# MCU025B_F280049C_Device.net
KiCad netlist of a schematic drawn in Altium Designer
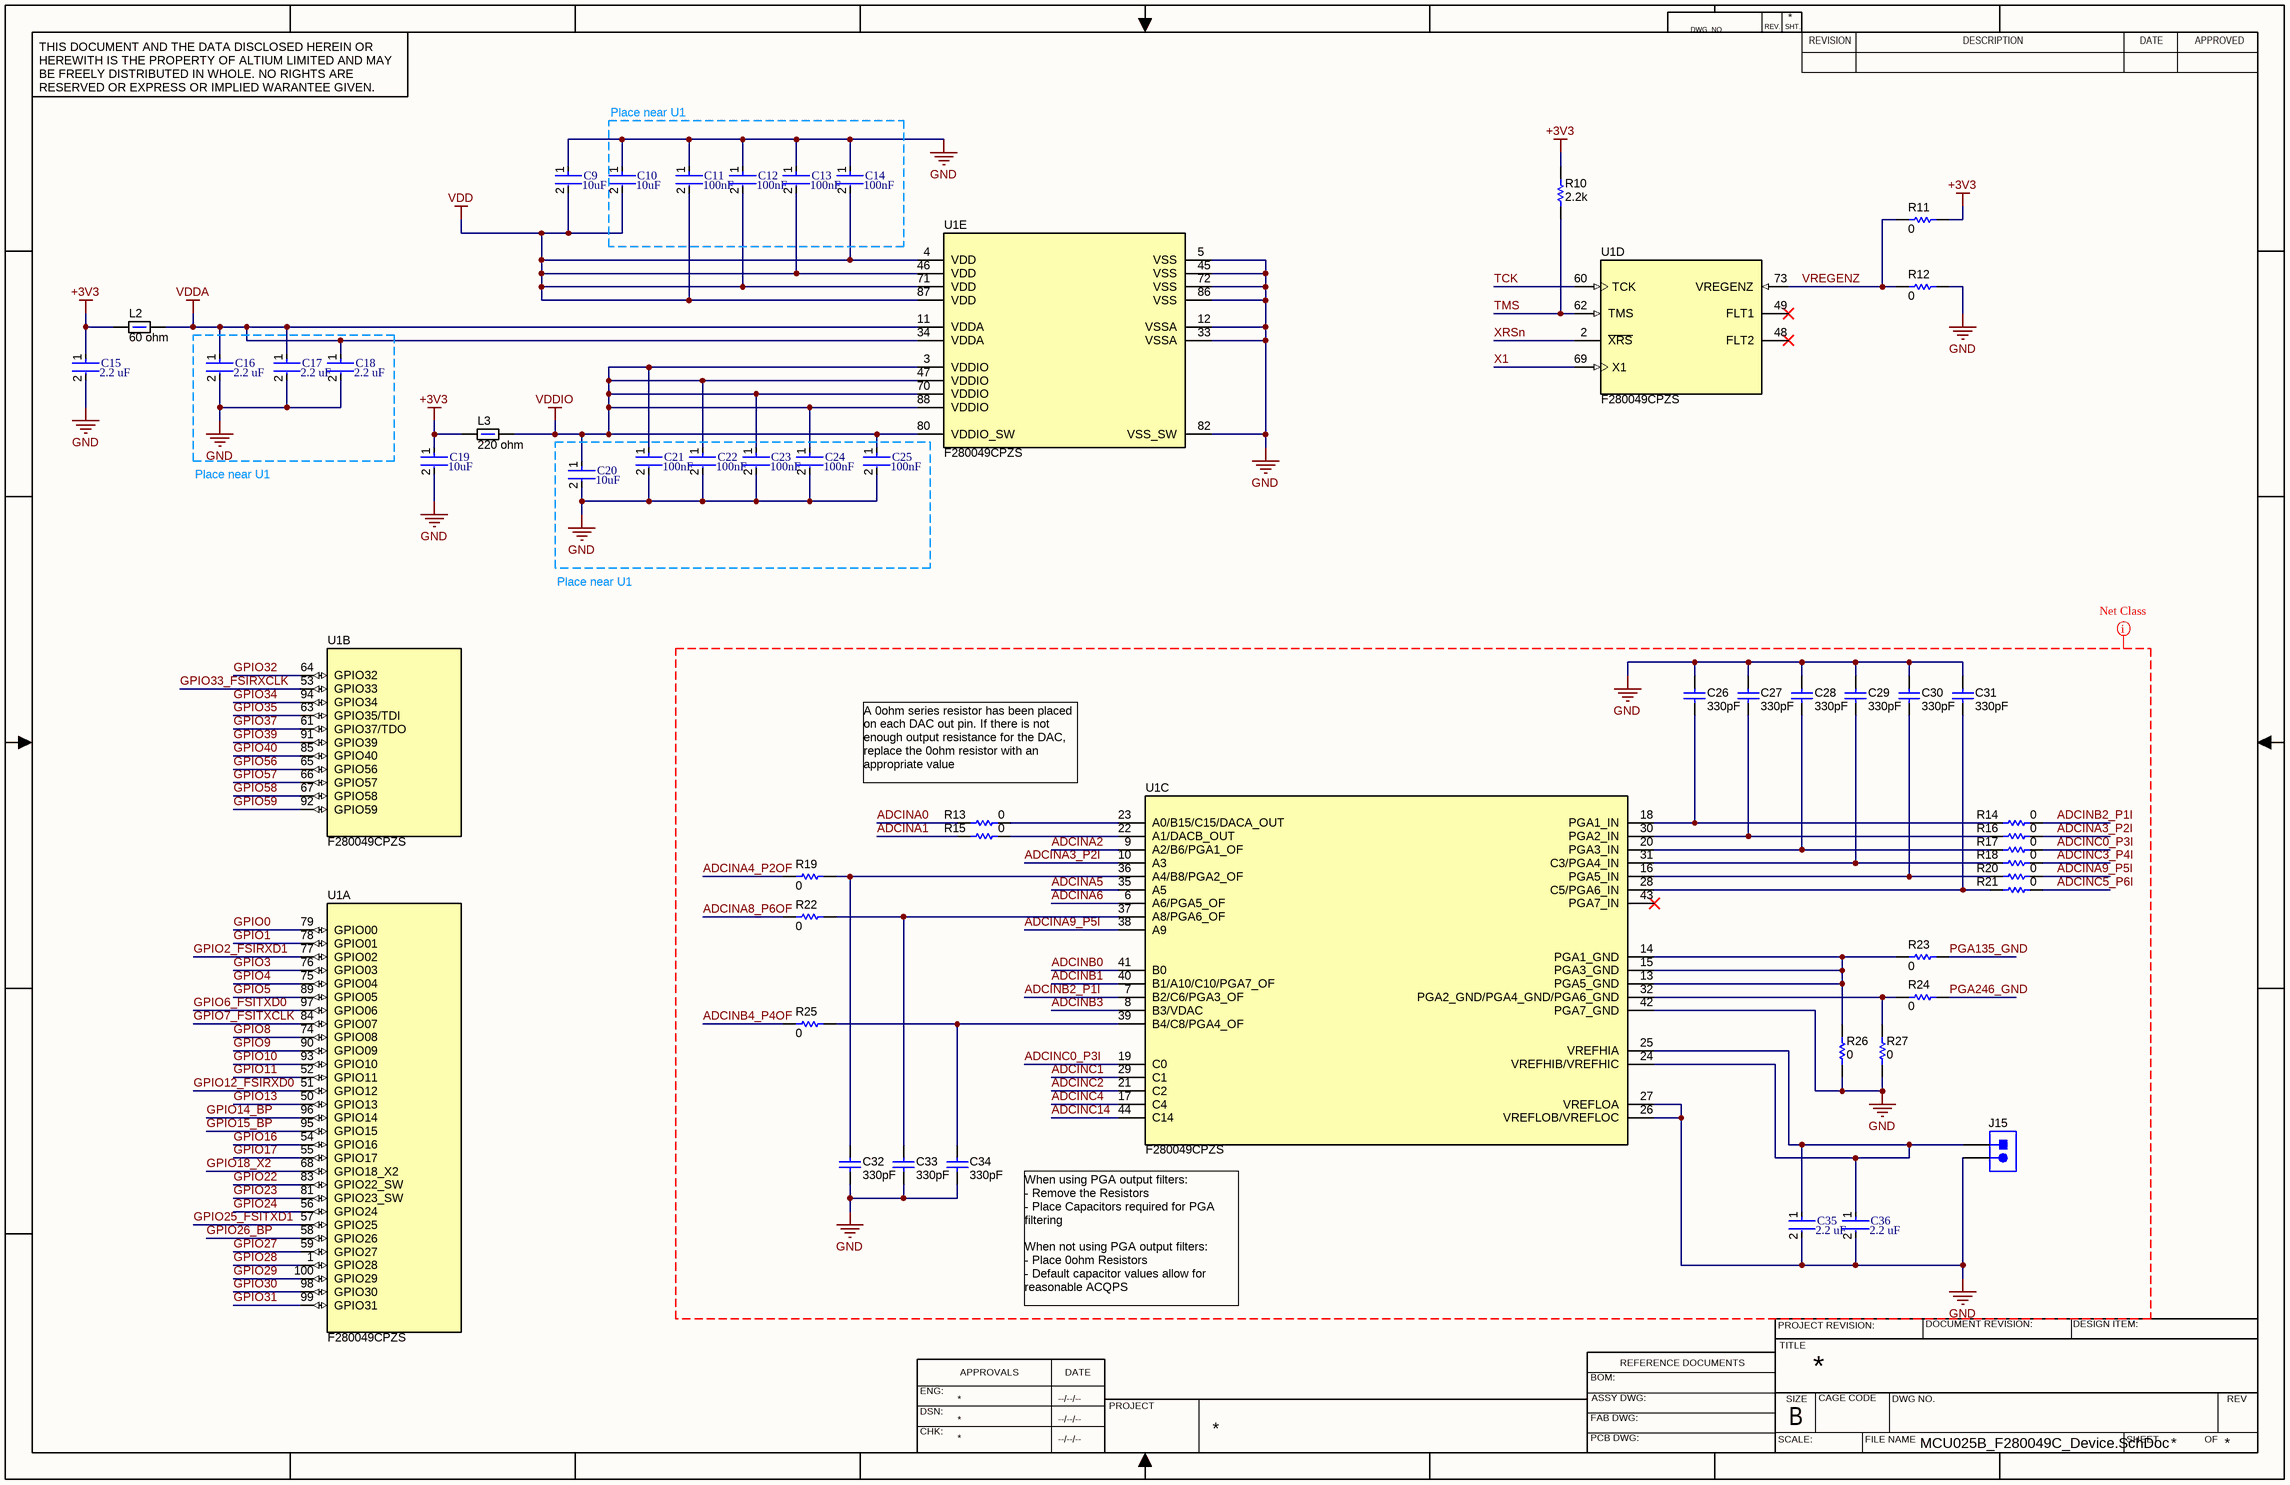
[diagram p0: MCU025B_F280049C_Device.SchDoc]

(export (version "E")
  (design (tool "Eeschema 10.0.6"))
  (components
    (comp (ref "C9")
      (value "GRM188R61A106ME69D")
      (footprint "FP-GRM188-0_15-MFG")
      (description "Chip Multilayer Ceramic Capacitors for General Purpose, 0603, 10uF, X5R, 15%, 20%, 10V")
      (fields (field (name "TOLERANCE") "20%") (field (name "CAPACITANCE") "10uF"))
      (libsource (lib "Altium Content Vault") (part "02cd4be3c70576c341d710602a673aa"))
    )
    (comp (ref "C10")
      (value "GRM188R61A106ME69D")
      (footprint "FP-GRM188-0_15-MFG")
      (description "Chip Multilayer Ceramic Capacitors for General Purpose, 0603, 10uF, X5R, 15%, 20%, 10V")
      (fields (field (name "TOLERANCE") "20%") (field (name "CAPACITANCE") "10uF"))
      (libsource (lib "Altium Content Vault") (part "02cd4be3c70576c341d710602a673aa"))
    )
    (comp (ref "C11")
      (value "CL10B104KA8NFNC")
      (footprint "FP-CL10-IPC_C")
      (description "Cap Ceramic 100nF 25V X7R ±10% Pad SMD 0603 +125°C T/R")
      (fields (field (name "TOLERANCE") "10%") (field (name "CAPACITANCE") "100nF"))
      (libsource (lib "Altium Content Vault") (part "b4654b650e69147ec39a6b967a45e02"))
    )
    (comp (ref "C12")
      (value "CL10B104KA8NFNC")
      (footprint "FP-CL10-IPC_C")
      (description "Cap Ceramic 100nF 25V X7R ±10% Pad SMD 0603 +125°C T/R")
      (fields (field (name "TOLERANCE") "10%") (field (name "CAPACITANCE") "100nF"))
      (libsource (lib "Altium Content Vault") (part "b4654b650e69147ec39a6b967a45e02"))
    )
    (comp (ref "C13")
      (value "CL10B104KA8NFNC")
      (footprint "FP-CL10-IPC_C")
      (description "Cap Ceramic 100nF 25V X7R ±10% Pad SMD 0603 +125°C T/R")
      (fields (field (name "TOLERANCE") "10%") (field (name "CAPACITANCE") "100nF"))
      (libsource (lib "Altium Content Vault") (part "b4654b650e69147ec39a6b967a45e02"))
    )
    (comp (ref "C14")
      (value "CL10B104KA8NFNC")
      (footprint "FP-CL10-IPC_C")
      (description "Cap Ceramic 100nF 25V X7R ±10% Pad SMD 0603 +125°C T/R")
      (fields (field (name "TOLERANCE") "10%") (field (name "CAPACITANCE") "100nF"))
      (libsource (lib "Altium Content Vault") (part "b4654b650e69147ec39a6b967a45e02"))
    )
    (comp (ref "C15")
      (value "CC0805KKX7R5BB225")
      (footprint "FP-CC0805-0_85-MFG")
      (description "CAP CER 2.2UF 6.3V X7R 0805")
      (fields
        (field (name "TOLERANCE") "0.1")
        (field (name "OCTOPART") "https://octopart.com/cc0805kkx7r5bb225-yageo-29810442")
        (field (name "CAPACITANCE") "2.2 uF")
      )
      (libsource (lib "Altium Content Vault") (part "11868f565c42a9108669ba33697ecf6"))
    )
    (comp (ref "C16")
      (value "CC0805KKX7R5BB225")
      (footprint "FP-CC0805-0_85-MFG")
      (description "CAP CER 2.2UF 6.3V X7R 0805")
      (fields
        (field (name "TOLERANCE") "0.1")
        (field (name "OCTOPART") "https://octopart.com/cc0805kkx7r5bb225-yageo-29810442")
        (field (name "CAPACITANCE") "2.2 uF")
      )
      (libsource (lib "Altium Content Vault") (part "11868f565c42a9108669ba33697ecf6"))
    )
    (comp (ref "C17")
      (value "CC0805KKX7R5BB225")
      (footprint "FP-CC0805-0_85-MFG")
      (description "CAP CER 2.2UF 6.3V X7R 0805")
      (fields
        (field (name "TOLERANCE") "0.1")
        (field (name "OCTOPART") "https://octopart.com/cc0805kkx7r5bb225-yageo-29810442")
        (field (name "CAPACITANCE") "2.2 uF")
      )
      (libsource (lib "Altium Content Vault") (part "11868f565c42a9108669ba33697ecf6"))
    )
    (comp (ref "C18")
      (value "CC0805KKX7R5BB225")
      (footprint "FP-CC0805-0_85-MFG")
      (description "CAP CER 2.2UF 6.3V X7R 0805")
      (fields
        (field (name "TOLERANCE") "0.1")
        (field (name "OCTOPART") "https://octopart.com/cc0805kkx7r5bb225-yageo-29810442")
        (field (name "CAPACITANCE") "2.2 uF")
      )
      (libsource (lib "Altium Content Vault") (part "11868f565c42a9108669ba33697ecf6"))
    )
    (comp (ref "C19")
      (value "GRM188R61A106ME69D")
      (footprint "FP-GRM188-0_15-MFG")
      (description "Chip Multilayer Ceramic Capacitors for General Purpose, 0603, 10uF, X5R, 15%, 20%, 10V")
      (fields (field (name "TOLERANCE") "20%") (field (name "CAPACITANCE") "10uF"))
      (libsource (lib "Altium Content Vault") (part "02cd4be3c70576c341d710602a673aa"))
    )
    (comp (ref "C20")
      (value "GRM188R61A106ME69D")
      (footprint "FP-GRM188-0_15-MFG")
      (description "Chip Multilayer Ceramic Capacitors for General Purpose, 0603, 10uF, X5R, 15%, 20%, 10V")
      (fields (field (name "TOLERANCE") "20%") (field (name "CAPACITANCE") "10uF"))
      (libsource (lib "Altium Content Vault") (part "02cd4be3c70576c341d710602a673aa"))
    )
    (comp (ref "C21")
      (value "CL10B104KA8NFNC")
      (footprint "FP-CL10-IPC_C")
      (description "Cap Ceramic 100nF 25V X7R ±10% Pad SMD 0603 +125°C T/R")
      (fields (field (name "TOLERANCE") "10%") (field (name "CAPACITANCE") "100nF"))
      (libsource (lib "Altium Content Vault") (part "b4654b650e69147ec39a6b967a45e02"))
    )
    (comp (ref "C22")
      (value "CL10B104KA8NFNC")
      (footprint "FP-CL10-IPC_C")
      (description "Cap Ceramic 100nF 25V X7R ±10% Pad SMD 0603 +125°C T/R")
      (fields (field (name "TOLERANCE") "10%") (field (name "CAPACITANCE") "100nF"))
      (libsource (lib "Altium Content Vault") (part "b4654b650e69147ec39a6b967a45e02"))
    )
    (comp (ref "C23")
      (value "CL10B104KA8NFNC")
      (footprint "FP-CL10-IPC_C")
      (description "Cap Ceramic 100nF 25V X7R ±10% Pad SMD 0603 +125°C T/R")
      (fields (field (name "TOLERANCE") "10%") (field (name "CAPACITANCE") "100nF"))
      (libsource (lib "Altium Content Vault") (part "b4654b650e69147ec39a6b967a45e02"))
    )
    (comp (ref "C24")
      (value "CL10B104KA8NFNC")
      (footprint "FP-CL10-IPC_C")
      (description "Cap Ceramic 100nF 25V X7R ±10% Pad SMD 0603 +125°C T/R")
      (fields (field (name "TOLERANCE") "10%") (field (name "CAPACITANCE") "100nF"))
      (libsource (lib "Altium Content Vault") (part "b4654b650e69147ec39a6b967a45e02"))
    )
    (comp (ref "C25")
      (value "CL10B104KA8NFNC")
      (footprint "FP-CL10-IPC_C")
      (description "Cap Ceramic 100nF 25V X7R ±10% Pad SMD 0603 +125°C T/R")
      (fields (field (name "TOLERANCE") "10%") (field (name "CAPACITANCE") "100nF"))
      (libsource (lib "Altium Content Vault") (part "b4654b650e69147ec39a6b967a45e02"))
    )
    (comp (ref "C26")
      (value "GRM1885C1H331JA01D")
      (footprint "0603")
      (description "CAP, CERM, 330 pF, 50 V, +/- 5%, C0G/NP0, 0603")
      (fields
        (field (name "VALUEDISPLAYED") "330pF")
        (field (name "MANUFACTURER") "MuRata")
        (field (name "PUBLISHER") "Texas Instruments")
      )
      (libsource (lib "Altium Vault - TI") (part "Capacitor"))
    )
    (comp (ref "C27")
      (value "GRM1885C1H331JA01D")
      (footprint "0603")
      (description "CAP, CERM, 330 pF, 50 V, +/- 5%, C0G/NP0, 0603")
      (fields
        (field (name "VALUEDISPLAYED") "330pF")
        (field (name "MANUFACTURER") "MuRata")
        (field (name "PUBLISHER") "Texas Instruments")
      )
      (libsource (lib "Altium Vault - TI") (part "Capacitor"))
    )
    (comp (ref "C28")
      (value "GRM1885C1H331JA01D")
      (footprint "0603")
      (description "CAP, CERM, 330 pF, 50 V, +/- 5%, C0G/NP0, 0603")
      (fields
        (field (name "VALUEDISPLAYED") "330pF")
        (field (name "MANUFACTURER") "MuRata")
        (field (name "PUBLISHER") "Texas Instruments")
      )
      (libsource (lib "Altium Vault - TI") (part "Capacitor"))
    )
    (comp (ref "C29")
      (value "GRM1885C1H331JA01D")
      (footprint "0603")
      (description "CAP, CERM, 330 pF, 50 V, +/- 5%, C0G/NP0, 0603")
      (fields
        (field (name "VALUEDISPLAYED") "330pF")
        (field (name "MANUFACTURER") "MuRata")
        (field (name "PUBLISHER") "Texas Instruments")
      )
      (libsource (lib "Altium Vault - TI") (part "Capacitor"))
    )
    (comp (ref "C30")
      (value "GRM1885C1H331JA01D")
      (footprint "0603")
      (description "CAP, CERM, 330 pF, 50 V, +/- 5%, C0G/NP0, 0603")
      (fields
        (field (name "VALUEDISPLAYED") "330pF")
        (field (name "MANUFACTURER") "MuRata")
        (field (name "PUBLISHER") "Texas Instruments")
      )
      (libsource (lib "Altium Vault - TI") (part "Capacitor"))
    )
    (comp (ref "C31")
      (value "GRM1885C1H331JA01D")
      (footprint "0603")
      (description "CAP, CERM, 330 pF, 50 V, +/- 5%, C0G/NP0, 0603")
      (fields
        (field (name "VALUEDISPLAYED") "330pF")
        (field (name "MANUFACTURER") "MuRata")
        (field (name "PUBLISHER") "Texas Instruments")
      )
      (libsource (lib "Altium Vault - TI") (part "Capacitor"))
    )
    (comp (ref "C32")
      (value "GRM1885C1H331JA01D")
      (footprint "0603")
      (description "CAP, CERM, 330 pF, 50 V, +/- 5%, C0G/NP0, 0603")
      (fields
        (field (name "VALUEDISPLAYED") "330pF")
        (field (name "MANUFACTURER") "MuRata")
        (field (name "PUBLISHER") "Texas Instruments")
      )
      (libsource (lib "Altium Vault - TI") (part "Capacitor"))
    )
    (comp (ref "C33")
      (value "GRM1885C1H331JA01D")
      (footprint "0603")
      (description "CAP, CERM, 330 pF, 50 V, +/- 5%, C0G/NP0, 0603")
      (fields
        (field (name "VALUEDISPLAYED") "330pF")
        (field (name "MANUFACTURER") "MuRata")
        (field (name "PUBLISHER") "Texas Instruments")
      )
      (libsource (lib "Altium Vault - TI") (part "Capacitor"))
    )
    (comp (ref "C34")
      (value "GRM1885C1H331JA01D")
      (footprint "0603")
      (description "CAP, CERM, 330 pF, 50 V, +/- 5%, C0G/NP0, 0603")
      (fields
        (field (name "VALUEDISPLAYED") "330pF")
        (field (name "MANUFACTURER") "MuRata")
        (field (name "PUBLISHER") "Texas Instruments")
      )
      (libsource (lib "Altium Vault - TI") (part "Capacitor"))
    )
    (comp (ref "C35")
      (value "CC0805KKX7R5BB225")
      (footprint "FP-CC0805-0_85-MFG")
      (description "CAP CER 2.2UF 6.3V X7R 0805")
      (fields
        (field (name "TOLERANCE") "0.1")
        (field (name "OCTOPART") "https://octopart.com/cc0805kkx7r5bb225-yageo-29810442")
        (field (name "CAPACITANCE") "2.2 uF")
      )
      (libsource (lib "Altium Content Vault") (part "11868f565c42a9108669ba33697ecf6"))
    )
    (comp (ref "C36")
      (value "CC0805KKX7R5BB225")
      (footprint "FP-CC0805-0_85-MFG")
      (description "CAP CER 2.2UF 6.3V X7R 0805")
      (fields
        (field (name "TOLERANCE") "0.1")
        (field (name "OCTOPART") "https://octopart.com/cc0805kkx7r5bb225-yageo-29810442")
        (field (name "CAPACITANCE") "2.2 uF")
      )
      (libsource (lib "Altium Content Vault") (part "11868f565c42a9108669ba33697ecf6"))
    )
    (comp (ref "J15")
      (value "61300211121")
      (footprint "WURTH_61300211121")
      (description "Header, 2.54 mm, 2x1, Gold, TH")
      (fields (field (name "MANUFACTURER") "Wurth Elektronik") (field (name "PUBLISHER") "Texas Instruments"))
      (libsource (lib "Altium Vault - TI") (part "CMP-0054794-1"))
    )
    (comp (ref "L2")
      (value "BKP2125HS600-T")
      (footprint "0805")
      (description "Ferrite Bead, 60 ohm @ 100 MHz, 3 A, 0805")
      (fields
        (field (name "VALUEDISPLAYED") "60 ohm")
        (field (name "MANUFACTURER") "Taiyo Yuden")
        (field (name "PUBLISHER") "Texas Instruments")
      )
      (libsource (lib "Altium Vault - TI") (part "Ferrite_Bead"))
    )
    (comp (ref "L3")
      (value "BLM21PG221SN1D")
      (footprint "0805")
      (description "Ferrite Bead, 220 ohm @ 100 MHz, 2 A, 0805")
      (fields
        (field (name "VALUEDISPLAYED") "220 ohm")
        (field (name "MANUFACTURER") "MuRata")
        (field (name "PUBLISHER") "Texas Instruments")
      )
      (libsource (lib "Altium Vault - TI") (part "Ferrite_Bead"))
    )
    (comp (ref "R10")
      (value "CRCW04022K20JNED")
      (footprint "0402")
      (description "RES, 2.2 k, 5%, 0.063 W, AEC-Q200 Grade 0, 0402")
      (fields (field (name "VALUEDISPLAYED") "2.2k") (field (name "MANUFACTURER") "Vishay-Dale"))
      (libsource (lib "Altium Vault - TI") (part "Resistor"))
    )
    (comp (ref "R11")
      (value "CRCW06030000Z0EA")
      (footprint "0603")
      (description "RES, 0, 5%, 0.1 W, AEC-Q200 Grade 0, 0603")
      (fields (field (name "VALUEDISPLAYED") "0") (field (name "MANUFACTURER") "Vishay-Dale"))
      (libsource (lib "Altium Vault - TI") (part "Resistor"))
    )
    (comp (ref "R12")
      (value "CRCW06030000Z0EA")
      (footprint "0603")
      (description "RES, 0, 5%, 0.1 W, AEC-Q200 Grade 0, 0603")
      (fields (field (name "VALUEDISPLAYED") "0") (field (name "MANUFACTURER") "Vishay-Dale"))
      (libsource (lib "Altium Vault - TI") (part "Resistor"))
    )
    (comp (ref "R13")
      (value "CRCW06030000Z0EA")
      (footprint "0603")
      (description "RES, 0, 5%, 0.1 W, AEC-Q200 Grade 0, 0603")
      (fields (field (name "VALUEDISPLAYED") "0") (field (name "MANUFACTURER") "Vishay-Dale"))
      (libsource (lib "Altium Vault - TI") (part "Resistor"))
    )
    (comp (ref "R14")
      (value "CRCW06030000Z0EA")
      (footprint "0603")
      (description "RES, 0, 5%, 0.1 W, AEC-Q200 Grade 0, 0603")
      (fields (field (name "VALUEDISPLAYED") "0") (field (name "MANUFACTURER") "Vishay-Dale"))
      (libsource (lib "Altium Vault - TI") (part "Resistor"))
    )
    (comp (ref "R15")
      (value "CRCW06030000Z0EA")
      (footprint "0603")
      (description "RES, 0, 5%, 0.1 W, AEC-Q200 Grade 0, 0603")
      (fields (field (name "VALUEDISPLAYED") "0") (field (name "MANUFACTURER") "Vishay-Dale"))
      (libsource (lib "Altium Vault - TI") (part "Resistor"))
    )
    (comp (ref "R16")
      (value "CRCW06030000Z0EA")
      (footprint "0603")
      (description "RES, 0, 5%, 0.1 W, AEC-Q200 Grade 0, 0603")
      (fields (field (name "VALUEDISPLAYED") "0") (field (name "MANUFACTURER") "Vishay-Dale"))
      (libsource (lib "Altium Vault - TI") (part "Resistor"))
    )
    (comp (ref "R17")
      (value "CRCW06030000Z0EA")
      (footprint "0603")
      (description "RES, 0, 5%, 0.1 W, AEC-Q200 Grade 0, 0603")
      (fields (field (name "VALUEDISPLAYED") "0") (field (name "MANUFACTURER") "Vishay-Dale"))
      (libsource (lib "Altium Vault - TI") (part "Resistor"))
    )
    (comp (ref "R18")
      (value "CRCW06030000Z0EA")
      (footprint "0603")
      (description "RES, 0, 5%, 0.1 W, AEC-Q200 Grade 0, 0603")
      (fields (field (name "VALUEDISPLAYED") "0") (field (name "MANUFACTURER") "Vishay-Dale"))
      (libsource (lib "Altium Vault - TI") (part "Resistor"))
    )
    (comp (ref "R19")
      (value "CRCW06030000Z0EA")
      (footprint "0603")
      (description "RES, 0, 5%, 0.1 W, AEC-Q200 Grade 0, 0603")
      (fields (field (name "VALUEDISPLAYED") "0") (field (name "MANUFACTURER") "Vishay-Dale"))
      (libsource (lib "Altium Vault - TI") (part "Resistor"))
    )
    (comp (ref "R20")
      (value "CRCW06030000Z0EA")
      (footprint "0603")
      (description "RES, 0, 5%, 0.1 W, AEC-Q200 Grade 0, 0603")
      (fields (field (name "VALUEDISPLAYED") "0") (field (name "MANUFACTURER") "Vishay-Dale"))
      (libsource (lib "Altium Vault - TI") (part "Resistor"))
    )
    (comp (ref "R21")
      (value "CRCW06030000Z0EA")
      (footprint "0603")
      (description "RES, 0, 5%, 0.1 W, AEC-Q200 Grade 0, 0603")
      (fields (field (name "VALUEDISPLAYED") "0") (field (name "MANUFACTURER") "Vishay-Dale"))
      (libsource (lib "Altium Vault - TI") (part "Resistor"))
    )
    (comp (ref "R22")
      (value "CRCW06030000Z0EA")
      (footprint "0603")
      (description "RES, 0, 5%, 0.1 W, AEC-Q200 Grade 0, 0603")
      (fields (field (name "VALUEDISPLAYED") "0") (field (name "MANUFACTURER") "Vishay-Dale"))
      (libsource (lib "Altium Vault - TI") (part "Resistor"))
    )
    (comp (ref "R23")
      (value "CRCW06030000Z0EA")
      (footprint "0603")
      (description "RES, 0, 5%, 0.1 W, AEC-Q200 Grade 0, 0603")
      (fields (field (name "VALUEDISPLAYED") "0") (field (name "MANUFACTURER") "Vishay-Dale"))
      (libsource (lib "Altium Vault - TI") (part "Resistor"))
    )
    (comp (ref "R24")
      (value "CRCW06030000Z0EA")
      (footprint "0603")
      (description "RES, 0, 5%, 0.1 W, AEC-Q200 Grade 0, 0603")
      (fields (field (name "VALUEDISPLAYED") "0") (field (name "MANUFACTURER") "Vishay-Dale"))
      (libsource (lib "Altium Vault - TI") (part "Resistor"))
    )
    (comp (ref "R25")
      (value "CRCW06030000Z0EA")
      (footprint "0603")
      (description "RES, 0, 5%, 0.1 W, AEC-Q200 Grade 0, 0603")
      (fields (field (name "VALUEDISPLAYED") "0") (field (name "MANUFACTURER") "Vishay-Dale"))
      (libsource (lib "Altium Vault - TI") (part "Resistor"))
    )
    (comp (ref "R26")
      (value "CRCW06030000Z0EA")
      (footprint "0603")
      (description "RES, 0, 5%, 0.1 W, AEC-Q200 Grade 0, 0603")
      (fields (field (name "VALUEDISPLAYED") "0") (field (name "MANUFACTURER") "Vishay-Dale"))
      (libsource (lib "Altium Vault - TI") (part "Resistor"))
    )
    (comp (ref "R27")
      (value "CRCW06030000Z0EA")
      (footprint "0603")
      (description "RES, 0, 5%, 0.1 W, AEC-Q200 Grade 0, 0603")
      (fields (field (name "VALUEDISPLAYED") "0") (field (name "MANUFACTURER") "Vishay-Dale"))
      (libsource (lib "Altium Vault - TI") (part "Resistor"))
    )
    (comp (ref "U1")
      (value "F280049CPZS")
      (footprint "PZ0100A_N")
      (description "Piccolo Microcontroller, PZ0100A (LQFP-100)")
      (fields (field (name "PARTNUMBER") "F280049CPZS") (field (name "MANUFACTURER") "Texas Instruments"))
      (libsource (lib "Altium Vault - TI") (part "F280049PZ"))
    )
  )
  (nets
    (net (code "1") (name "+3V3") (class "Default")
      (node (ref "C15") (pin "1") (pinfunction "1_1") (pintype "passive"))
      (node (ref "C19") (pin "1") (pinfunction "1_1") (pintype "passive"))
      (node (ref "L2") (pin "1") (pinfunction "1_1") (pintype "passive"))
      (node (ref "L3") (pin "1") (pinfunction "1_1") (pintype "passive"))
      (node (ref "R10") (pin "2") (pinfunction "2_2") (pintype "passive"))
      (node (ref "R11") (pin "2") (pinfunction "2_2") (pintype "passive"))
    )
    (net (code "2") (name "/ADCINA0") (class "Default")
      (node (ref "R13") (pin "1") (pinfunction "1_1") (pintype "passive"))
    )
    (net (code "3") (name "/ADCINA1") (class "Default")
      (node (ref "R15") (pin "1") (pinfunction "1_1") (pintype "passive"))
    )
    (net (code "4") (name "/ADCINA2") (class "Default")
      (node (ref "U1") (pin "9") (pinfunction "A2/B6/PGA1_OF_9") (pintype "passive"))
    )
    (net (code "5") (name "/ADCINA3_P2I") (class "Default")
      (node (ref "R16") (pin "2") (pinfunction "2_2") (pintype "passive"))
      (node (ref "U1") (pin "10") (pinfunction "A3_10") (pintype "passive"))
    )
    (net (code "6") (name "/ADCINA4_P2OF") (class "Default")
      (node (ref "R19") (pin "1") (pinfunction "1_1") (pintype "passive"))
    )
    (net (code "7") (name "/ADCINA5") (class "Default")
      (node (ref "U1") (pin "35") (pinfunction "A5_35") (pintype "passive"))
    )
    (net (code "8") (name "/ADCINA6") (class "Default")
      (node (ref "U1") (pin "6") (pinfunction "A6/PGA5_OF_6") (pintype "passive"))
    )
    (net (code "9") (name "/ADCINA8_P6OF") (class "Default")
      (node (ref "R22") (pin "1") (pinfunction "1_1") (pintype "passive"))
    )
    (net (code "10") (name "/ADCINA9_P5I") (class "Default")
      (node (ref "R20") (pin "2") (pinfunction "2_2") (pintype "passive"))
      (node (ref "U1") (pin "38") (pinfunction "A9_38") (pintype "passive"))
    )
    (net (code "11") (name "/ADCINB0") (class "Default")
      (node (ref "U1") (pin "41") (pinfunction "B0_41") (pintype "passive"))
    )
    (net (code "12") (name "/ADCINB1") (class "Default")
      (node (ref "U1") (pin "40") (pinfunction "B1/A10/C10/PGA7_OF_40") (pintype "passive"))
    )
    (net (code "13") (name "/ADCINB2_P1I") (class "Default")
      (node (ref "R14") (pin "2") (pinfunction "2_2") (pintype "passive"))
      (node (ref "U1") (pin "7") (pinfunction "B2/C6/PGA3_OF_7") (pintype "passive"))
    )
    (net (code "14") (name "/ADCINB3") (class "Default")
      (node (ref "U1") (pin "8") (pinfunction "B3/VDAC_8") (pintype "passive"))
    )
    (net (code "15") (name "/ADCINB4_P4OF") (class "Default")
      (node (ref "R25") (pin "1") (pinfunction "1_1") (pintype "passive"))
    )
    (net (code "16") (name "/ADCINC0_P3I") (class "Default")
      (node (ref "R17") (pin "2") (pinfunction "2_2") (pintype "passive"))
      (node (ref "U1") (pin "19") (pinfunction "C0_19") (pintype "passive"))
    )
    (net (code "17") (name "/ADCINC1") (class "Default")
      (node (ref "U1") (pin "29") (pinfunction "C1_29") (pintype "passive"))
    )
    (net (code "18") (name "/ADCINC2") (class "Default")
      (node (ref "U1") (pin "21") (pinfunction "C2_21") (pintype "passive"))
    )
    (net (code "19") (name "/ADCINC3_P4I") (class "Default")
      (node (ref "R18") (pin "2") (pinfunction "2_2") (pintype "passive"))
    )
    (net (code "20") (name "/ADCINC4") (class "Default")
      (node (ref "U1") (pin "17") (pinfunction "C4_17") (pintype "passive"))
    )
    (net (code "21") (name "/ADCINC5_P6I") (class "Default")
      (node (ref "R21") (pin "2") (pinfunction "2_2") (pintype "passive"))
    )
    (net (code "22") (name "/ADCINC14") (class "Default")
      (node (ref "U1") (pin "44") (pinfunction "C14_44") (pintype "passive"))
    )
    (net (code "23") (name "/GPIO0") (class "Default")
      (node (ref "U1") (pin "79") (pinfunction "GPIO00_79") (pintype "bidirectional"))
    )
    (net (code "24") (name "/GPIO1") (class "Default")
      (node (ref "U1") (pin "78") (pinfunction "GPIO01_78") (pintype "bidirectional"))
    )
    (net (code "25") (name "/GPIO2_FSIRXD1") (class "Default")
      (node (ref "U1") (pin "77") (pinfunction "GPIO02_77") (pintype "bidirectional"))
    )
    (net (code "26") (name "/GPIO3") (class "Default")
      (node (ref "U1") (pin "76") (pinfunction "GPIO03_76") (pintype "bidirectional"))
    )
    (net (code "27") (name "/GPIO4") (class "Default")
      (node (ref "U1") (pin "75") (pinfunction "GPIO04_75") (pintype "bidirectional"))
    )
    (net (code "28") (name "/GPIO5") (class "Default")
      (node (ref "U1") (pin "89") (pinfunction "GPIO05_89") (pintype "bidirectional"))
    )
    (net (code "29") (name "/GPIO6_FSITXD0") (class "Default")
      (node (ref "U1") (pin "97") (pinfunction "GPIO06_97") (pintype "bidirectional"))
    )
    (net (code "30") (name "/GPIO7_FSITXCLK") (class "Default")
      (node (ref "U1") (pin "84") (pinfunction "GPIO07_84") (pintype "bidirectional"))
    )
    (net (code "31") (name "/GPIO8") (class "Default")
      (node (ref "U1") (pin "74") (pinfunction "GPIO08_74") (pintype "bidirectional"))
    )
    (net (code "32") (name "/GPIO9") (class "Default")
      (node (ref "U1") (pin "90") (pinfunction "GPIO09_90") (pintype "bidirectional"))
    )
    (net (code "33") (name "/GPIO10") (class "Default")
      (node (ref "U1") (pin "93") (pinfunction "GPIO10_93") (pintype "bidirectional"))
    )
    (net (code "34") (name "/GPIO11") (class "Default")
      (node (ref "U1") (pin "52") (pinfunction "GPIO11_52") (pintype "bidirectional"))
    )
    (net (code "35") (name "/GPIO12_FSIRXD0") (class "Default")
      (node (ref "U1") (pin "51") (pinfunction "GPIO12_51") (pintype "bidirectional"))
    )
    (net (code "36") (name "/GPIO13") (class "Default")
      (node (ref "U1") (pin "50") (pinfunction "GPIO13_50") (pintype "bidirectional"))
    )
    (net (code "37") (name "/GPIO14_BP") (class "Default")
      (node (ref "U1") (pin "96") (pinfunction "GPIO14_96") (pintype "bidirectional"))
    )
    (net (code "38") (name "/GPIO15_BP") (class "Default")
      (node (ref "U1") (pin "95") (pinfunction "GPIO15_95") (pintype "bidirectional"))
    )
    (net (code "39") (name "/GPIO16") (class "Default")
      (node (ref "U1") (pin "54") (pinfunction "GPIO16_54") (pintype "bidirectional"))
    )
    (net (code "40") (name "/GPIO17") (class "Default")
      (node (ref "U1") (pin "55") (pinfunction "GPIO17_55") (pintype "bidirectional"))
    )
    (net (code "41") (name "/GPIO18_X2") (class "Default")
      (node (ref "U1") (pin "68") (pinfunction "GPIO18_X2_68") (pintype "bidirectional"))
    )
    (net (code "42") (name "/GPIO22") (class "Default")
      (node (ref "U1") (pin "83") (pinfunction "GPIO22_SW_83") (pintype "bidirectional"))
    )
    (net (code "43") (name "/GPIO23") (class "Default")
      (node (ref "U1") (pin "81") (pinfunction "GPIO23_SW_81") (pintype "bidirectional"))
    )
    (net (code "44") (name "/GPIO24") (class "Default")
      (node (ref "U1") (pin "56") (pinfunction "GPIO24_56") (pintype "bidirectional"))
    )
    (net (code "45") (name "/GPIO25_FSITXD1") (class "Default")
      (node (ref "U1") (pin "57") (pinfunction "GPIO25_57") (pintype "bidirectional"))
    )
    (net (code "46") (name "/GPIO26_BP") (class "Default")
      (node (ref "U1") (pin "58") (pinfunction "GPIO26_58") (pintype "bidirectional"))
    )
    (net (code "47") (name "/GPIO27") (class "Default")
      (node (ref "U1") (pin "59") (pinfunction "GPIO27_59") (pintype "bidirectional"))
    )
    (net (code "48") (name "/GPIO28") (class "Default")
      (node (ref "U1") (pin "1") (pinfunction "GPIO28_1") (pintype "bidirectional"))
    )
    (net (code "49") (name "/GPIO29") (class "Default")
      (node (ref "U1") (pin "100") (pinfunction "GPIO29_100") (pintype "bidirectional"))
    )
    (net (code "50") (name "/GPIO30") (class "Default")
      (node (ref "U1") (pin "98") (pinfunction "GPIO30_98") (pintype "bidirectional"))
    )
    (net (code "51") (name "/GPIO31") (class "Default")
      (node (ref "U1") (pin "99") (pinfunction "GPIO31_99") (pintype "bidirectional"))
    )
    (net (code "52") (name "/GPIO32") (class "Default")
      (node (ref "U1") (pin "64") (pinfunction "GPIO32_64") (pintype "bidirectional"))
    )
    (net (code "53") (name "/GPIO33_FSIRXCLK") (class "Default")
      (node (ref "U1") (pin "53") (pinfunction "GPIO33_53") (pintype "bidirectional"))
    )
    (net (code "54") (name "/GPIO34") (class "Default")
      (node (ref "U1") (pin "94") (pinfunction "GPIO34_94") (pintype "bidirectional"))
    )
    (net (code "55") (name "/GPIO35") (class "Default")
      (node (ref "U1") (pin "63") (pinfunction "GPIO35/TDI_63") (pintype "bidirectional"))
    )
    (net (code "56") (name "/GPIO37") (class "Default")
      (node (ref "U1") (pin "61") (pinfunction "GPIO37/TDO_61") (pintype "bidirectional"))
    )
    (net (code "57") (name "/GPIO39") (class "Default")
      (node (ref "U1") (pin "91") (pinfunction "GPIO39_91") (pintype "bidirectional"))
    )
    (net (code "58") (name "/GPIO40") (class "Default")
      (node (ref "U1") (pin "85") (pinfunction "GPIO40_85") (pintype "bidirectional"))
    )
    (net (code "59") (name "/GPIO56") (class "Default")
      (node (ref "U1") (pin "65") (pinfunction "GPIO56_65") (pintype "bidirectional"))
    )
    (net (code "60") (name "/GPIO57") (class "Default")
      (node (ref "U1") (pin "66") (pinfunction "GPIO57_66") (pintype "bidirectional"))
    )
    (net (code "61") (name "/GPIO58") (class "Default")
      (node (ref "U1") (pin "67") (pinfunction "GPIO58_67") (pintype "bidirectional"))
    )
    (net (code "62") (name "/GPIO59") (class "Default")
      (node (ref "U1") (pin "92") (pinfunction "GPIO59_92") (pintype "bidirectional"))
    )
    (net (code "63") (name "/PGA135_GND") (class "Default")
      (node (ref "R23") (pin "2") (pinfunction "2_2") (pintype "passive"))
    )
    (net (code "64") (name "/PGA246_GND") (class "Default")
      (node (ref "R24") (pin "2") (pinfunction "2_2") (pintype "passive"))
    )
    (net (code "65") (name "/TCK") (class "Default")
      (node (ref "U1") (pin "60") (pinfunction "TCK_60") (pintype "input"))
    )
    (net (code "66") (name "/TMS") (class "Default")
      (node (ref "R10") (pin "1") (pinfunction "1_1") (pintype "passive"))
      (node (ref "U1") (pin "62") (pinfunction "TMS_62") (pintype "input"))
    )
    (net (code "67") (name "/VREGENZ") (class "Default")
      (node (ref "R11") (pin "1") (pinfunction "1_1") (pintype "passive"))
      (node (ref "R12") (pin "1") (pinfunction "1_1") (pintype "passive"))
      (node (ref "U1") (pin "73") (pinfunction "VREGENZ_73") (pintype "input"))
    )
    (net (code "68") (name "/X1") (class "Default")
      (node (ref "U1") (pin "69") (pinfunction "X1_69") (pintype "input"))
    )
    (net (code "69") (name "/XRSn") (class "Default")
      (node (ref "U1") (pin "2") (pinfunction "XRS_2") (pintype "open_collector"))
    )
    (net (code "70") (name "GND") (class "Default")
      (node (ref "C10") (pin "1") (pinfunction "1_1") (pintype "passive"))
      (node (ref "C11") (pin "1") (pinfunction "1_1") (pintype "passive"))
      (node (ref "C12") (pin "1") (pinfunction "1_1") (pintype "passive"))
      (node (ref "C13") (pin "1") (pinfunction "1_1") (pintype "passive"))
      (node (ref "C14") (pin "1") (pinfunction "1_1") (pintype "passive"))
      (node (ref "C15") (pin "2") (pinfunction "2_2") (pintype "passive"))
      (node (ref "C16") (pin "2") (pinfunction "2_2") (pintype "passive"))
      (node (ref "C17") (pin "2") (pinfunction "2_2") (pintype "passive"))
      (node (ref "C18") (pin "2") (pinfunction "2_2") (pintype "passive"))
      (node (ref "C19") (pin "2") (pinfunction "2_2") (pintype "passive"))
      (node (ref "C20") (pin "2") (pinfunction "2_2") (pintype "passive"))
      (node (ref "C21") (pin "2") (pinfunction "2_2") (pintype "passive"))
      (node (ref "C22") (pin "2") (pinfunction "2_2") (pintype "passive"))
      (node (ref "C23") (pin "2") (pinfunction "2_2") (pintype "passive"))
      (node (ref "C24") (pin "2") (pinfunction "2_2") (pintype "passive"))
      (node (ref "C25") (pin "2") (pinfunction "2_2") (pintype "passive"))
      (node (ref "C26") (pin "1") (pinfunction "1_1") (pintype "passive"))
      (node (ref "C27") (pin "1") (pinfunction "1_1") (pintype "passive"))
      (node (ref "C28") (pin "1") (pinfunction "1_1") (pintype "passive"))
      (node (ref "C29") (pin "1") (pinfunction "1_1") (pintype "passive"))
      (node (ref "C30") (pin "1") (pinfunction "1_1") (pintype "passive"))
      (node (ref "C31") (pin "1") (pinfunction "1_1") (pintype "passive"))
      (node (ref "C32") (pin "2") (pinfunction "2_2") (pintype "passive"))
      (node (ref "C33") (pin "2") (pinfunction "2_2") (pintype "passive"))
      (node (ref "C34") (pin "2") (pinfunction "2_2") (pintype "passive"))
      (node (ref "C35") (pin "2") (pinfunction "2_2") (pintype "passive"))
      (node (ref "C36") (pin "2") (pinfunction "2_2") (pintype "passive"))
      (node (ref "C9") (pin "1") (pinfunction "1_1") (pintype "passive"))
      (node (ref "J15") (pin "2") (pinfunction "2_2") (pintype "passive"))
      (node (ref "R12") (pin "2") (pinfunction "2_2") (pintype "passive"))
      (node (ref "R26") (pin "1") (pinfunction "1_1") (pintype "passive"))
      (node (ref "R27") (pin "1") (pinfunction "1_1") (pintype "passive"))
      (node (ref "U1") (pin "12") (pinfunction "VSSA_12") (pintype "power_in"))
      (node (ref "U1") (pin "26") (pinfunction "VREFLOB/VREFLOC_26") (pintype "passive"))
      (node (ref "U1") (pin "27") (pinfunction "VREFLOA_27") (pintype "passive"))
      (node (ref "U1") (pin "33") (pinfunction "VSSA_33") (pintype "power_in"))
      (node (ref "U1") (pin "42") (pinfunction "PGA7_GND_42") (pintype "passive"))
      (node (ref "U1") (pin "45") (pinfunction "VSS_45") (pintype "power_in"))
      (node (ref "U1") (pin "5") (pinfunction "VSS_5") (pintype "power_in"))
      (node (ref "U1") (pin "72") (pinfunction "VSS_72") (pintype "power_in"))
      (node (ref "U1") (pin "82") (pinfunction "VSS_SW_82") (pintype "power_in"))
      (node (ref "U1") (pin "86") (pinfunction "VSS_86") (pintype "power_in"))
    )
    (net (code "71") (name "Net-(U1C-A0{slash}B15{slash}C15{slash}DACA_OUT)") (class "Default")
      (node (ref "R13") (pin "2") (pinfunction "2_2") (pintype "passive"))
      (node (ref "U1") (pin "23") (pinfunction "A0/B15/C15/DACA_OUT_23") (pintype "passive"))
    )
    (net (code "72") (name "Net-(U1C-A1{slash}DACB_OUT)") (class "Default")
      (node (ref "R15") (pin "2") (pinfunction "2_2") (pintype "passive"))
      (node (ref "U1") (pin "22") (pinfunction "A1/DACB_OUT_22") (pintype "passive"))
    )
    (net (code "73") (name "Net-(U1C-A4{slash}B8{slash}PGA2_OF)") (class "Default")
      (node (ref "C32") (pin "1") (pinfunction "1_1") (pintype "passive"))
      (node (ref "R19") (pin "2") (pinfunction "2_2") (pintype "passive"))
      (node (ref "U1") (pin "36") (pinfunction "A4/B8/PGA2_OF_36") (pintype "passive"))
    )
    (net (code "74") (name "Net-(U1C-A8{slash}PGA6_OF)") (class "Default")
      (node (ref "C33") (pin "1") (pinfunction "1_1") (pintype "passive"))
      (node (ref "R22") (pin "2") (pinfunction "2_2") (pintype "passive"))
      (node (ref "U1") (pin "37") (pinfunction "A8/PGA6_OF_37") (pintype "passive"))
    )
    (net (code "75") (name "Net-(U1C-B4{slash}C8{slash}PGA4_OF)") (class "Default")
      (node (ref "C34") (pin "1") (pinfunction "1_1") (pintype "passive"))
      (node (ref "R25") (pin "2") (pinfunction "2_2") (pintype "passive"))
      (node (ref "U1") (pin "39") (pinfunction "B4/C8/PGA4_OF_39") (pintype "passive"))
    )
    (net (code "76") (name "Net-(U1C-C3{slash}PGA4_IN)") (class "Default")
      (node (ref "C29") (pin "2") (pinfunction "2_2") (pintype "passive"))
      (node (ref "R18") (pin "1") (pinfunction "1_1") (pintype "passive"))
      (node (ref "U1") (pin "31") (pinfunction "C3/PGA4_IN_31") (pintype "passive"))
    )
    (net (code "77") (name "Net-(U1C-C5{slash}PGA6_IN)") (class "Default")
      (node (ref "C31") (pin "2") (pinfunction "2_2") (pintype "passive"))
      (node (ref "R21") (pin "1") (pinfunction "1_1") (pintype "passive"))
      (node (ref "U1") (pin "28") (pinfunction "C5/PGA6_IN_28") (pintype "passive"))
    )
    (net (code "78") (name "Net-(U1C-PGA1_GND)") (class "Default")
      (node (ref "R23") (pin "1") (pinfunction "1_1") (pintype "passive"))
      (node (ref "R26") (pin "2") (pinfunction "2_2") (pintype "passive"))
      (node (ref "U1") (pin "13") (pinfunction "PGA5_GND_13") (pintype "passive"))
      (node (ref "U1") (pin "14") (pinfunction "PGA1_GND_14") (pintype "passive"))
      (node (ref "U1") (pin "15") (pinfunction "PGA3_GND_15") (pintype "passive"))
    )
    (net (code "79") (name "Net-(U1C-PGA1_IN)") (class "Default")
      (node (ref "C26") (pin "2") (pinfunction "2_2") (pintype "passive"))
      (node (ref "R14") (pin "1") (pinfunction "1_1") (pintype "passive"))
      (node (ref "U1") (pin "18") (pinfunction "PGA1_IN_18") (pintype "passive"))
    )
    (net (code "80") (name "Net-(U1C-PGA2_GND{slash}PGA4_GND{slash}PGA6_GND)") (class "Default")
      (node (ref "R24") (pin "1") (pinfunction "1_1") (pintype "passive"))
      (node (ref "R27") (pin "2") (pinfunction "2_2") (pintype "passive"))
      (node (ref "U1") (pin "32") (pinfunction "PGA2_GND/PGA4_GND/PGA6_GND_32") (pintype "passive"))
    )
    (net (code "81") (name "Net-(U1C-PGA2_IN)") (class "Default")
      (node (ref "C27") (pin "2") (pinfunction "2_2") (pintype "passive"))
      (node (ref "R16") (pin "1") (pinfunction "1_1") (pintype "passive"))
      (node (ref "U1") (pin "30") (pinfunction "PGA2_IN_30") (pintype "passive"))
    )
    (net (code "82") (name "Net-(U1C-PGA3_IN)") (class "Default")
      (node (ref "C28") (pin "2") (pinfunction "2_2") (pintype "passive"))
      (node (ref "R17") (pin "1") (pinfunction "1_1") (pintype "passive"))
      (node (ref "U1") (pin "20") (pinfunction "PGA3_IN_20") (pintype "passive"))
    )
    (net (code "83") (name "Net-(U1C-PGA5_IN)") (class "Default")
      (node (ref "C30") (pin "2") (pinfunction "2_2") (pintype "passive"))
      (node (ref "R20") (pin "1") (pinfunction "1_1") (pintype "passive"))
      (node (ref "U1") (pin "16") (pinfunction "PGA5_IN_16") (pintype "passive"))
    )
    (net (code "84") (name "Net-(U1C-VREFHIA)") (class "Default")
      (node (ref "C35") (pin "1") (pinfunction "1_1") (pintype "passive"))
      (node (ref "C36") (pin "1") (pinfunction "1_1") (pintype "passive"))
      (node (ref "J15") (pin "1") (pinfunction "1_1") (pintype "passive"))
      (node (ref "U1") (pin "24") (pinfunction "VREFHIB/VREFHIC_24") (pintype "passive"))
      (node (ref "U1") (pin "25") (pinfunction "VREFHIA_25") (pintype "passive"))
    )
    (net (code "85") (name "VDD") (class "Default")
      (node (ref "C10") (pin "2") (pinfunction "2_2") (pintype "passive"))
      (node (ref "C11") (pin "2") (pinfunction "2_2") (pintype "passive"))
      (node (ref "C12") (pin "2") (pinfunction "2_2") (pintype "passive"))
      (node (ref "C13") (pin "2") (pinfunction "2_2") (pintype "passive"))
      (node (ref "C14") (pin "2") (pinfunction "2_2") (pintype "passive"))
      (node (ref "C9") (pin "2") (pinfunction "2_2") (pintype "passive"))
      (node (ref "U1") (pin "4") (pinfunction "VDD_4") (pintype "power_in"))
      (node (ref "U1") (pin "46") (pinfunction "VDD_46") (pintype "power_in"))
      (node (ref "U1") (pin "71") (pinfunction "VDD_71") (pintype "power_in"))
      (node (ref "U1") (pin "87") (pinfunction "VDD_87") (pintype "power_in"))
    )
    (net (code "86") (name "VDDA") (class "Default")
      (node (ref "C16") (pin "1") (pinfunction "1_1") (pintype "passive"))
      (node (ref "C17") (pin "1") (pinfunction "1_1") (pintype "passive"))
      (node (ref "C18") (pin "1") (pinfunction "1_1") (pintype "passive"))
      (node (ref "L2") (pin "2") (pinfunction "2_2") (pintype "passive"))
      (node (ref "U1") (pin "11") (pinfunction "VDDA_11") (pintype "power_in"))
      (node (ref "U1") (pin "34") (pinfunction "VDDA_34") (pintype "power_in"))
    )
    (net (code "87") (name "VDDIO") (class "Default")
      (node (ref "C20") (pin "1") (pinfunction "1_1") (pintype "passive"))
      (node (ref "C21") (pin "1") (pinfunction "1_1") (pintype "passive"))
      (node (ref "C22") (pin "1") (pinfunction "1_1") (pintype "passive"))
      (node (ref "C23") (pin "1") (pinfunction "1_1") (pintype "passive"))
      (node (ref "C24") (pin "1") (pinfunction "1_1") (pintype "passive"))
      (node (ref "C25") (pin "1") (pinfunction "1_1") (pintype "passive"))
      (node (ref "L3") (pin "2") (pinfunction "2_2") (pintype "passive"))
      (node (ref "U1") (pin "3") (pinfunction "VDDIO_3") (pintype "power_in"))
      (node (ref "U1") (pin "47") (pinfunction "VDDIO_47") (pintype "power_in"))
      (node (ref "U1") (pin "70") (pinfunction "VDDIO_70") (pintype "power_in"))
      (node (ref "U1") (pin "80") (pinfunction "VDDIO_SW_80") (pintype "power_in"))
      (node (ref "U1") (pin "88") (pinfunction "VDDIO_88") (pintype "power_in"))
    )
    (net (code "88") (name "unconnected-(U1C-PGA7_IN-Pad43)") (class "Default")
      (node (ref "U1") (pin "43") (pinfunction "PGA7_IN_43") (pintype "passive+no_connect"))
    )
    (net (code "89") (name "unconnected-(U1D-FLT1-Pad49)") (class "Default")
      (node (ref "U1") (pin "49") (pinfunction "FLT1_49") (pintype "passive+no_connect"))
    )
    (net (code "90") (name "unconnected-(U1D-FLT2-Pad48)") (class "Default")
      (node (ref "U1") (pin "48") (pinfunction "FLT2_48") (pintype "passive+no_connect"))
    )
  )
)
